# Strombegrenzung_RevC.net
KiCad netlist of a schematic drawn in EAGLE
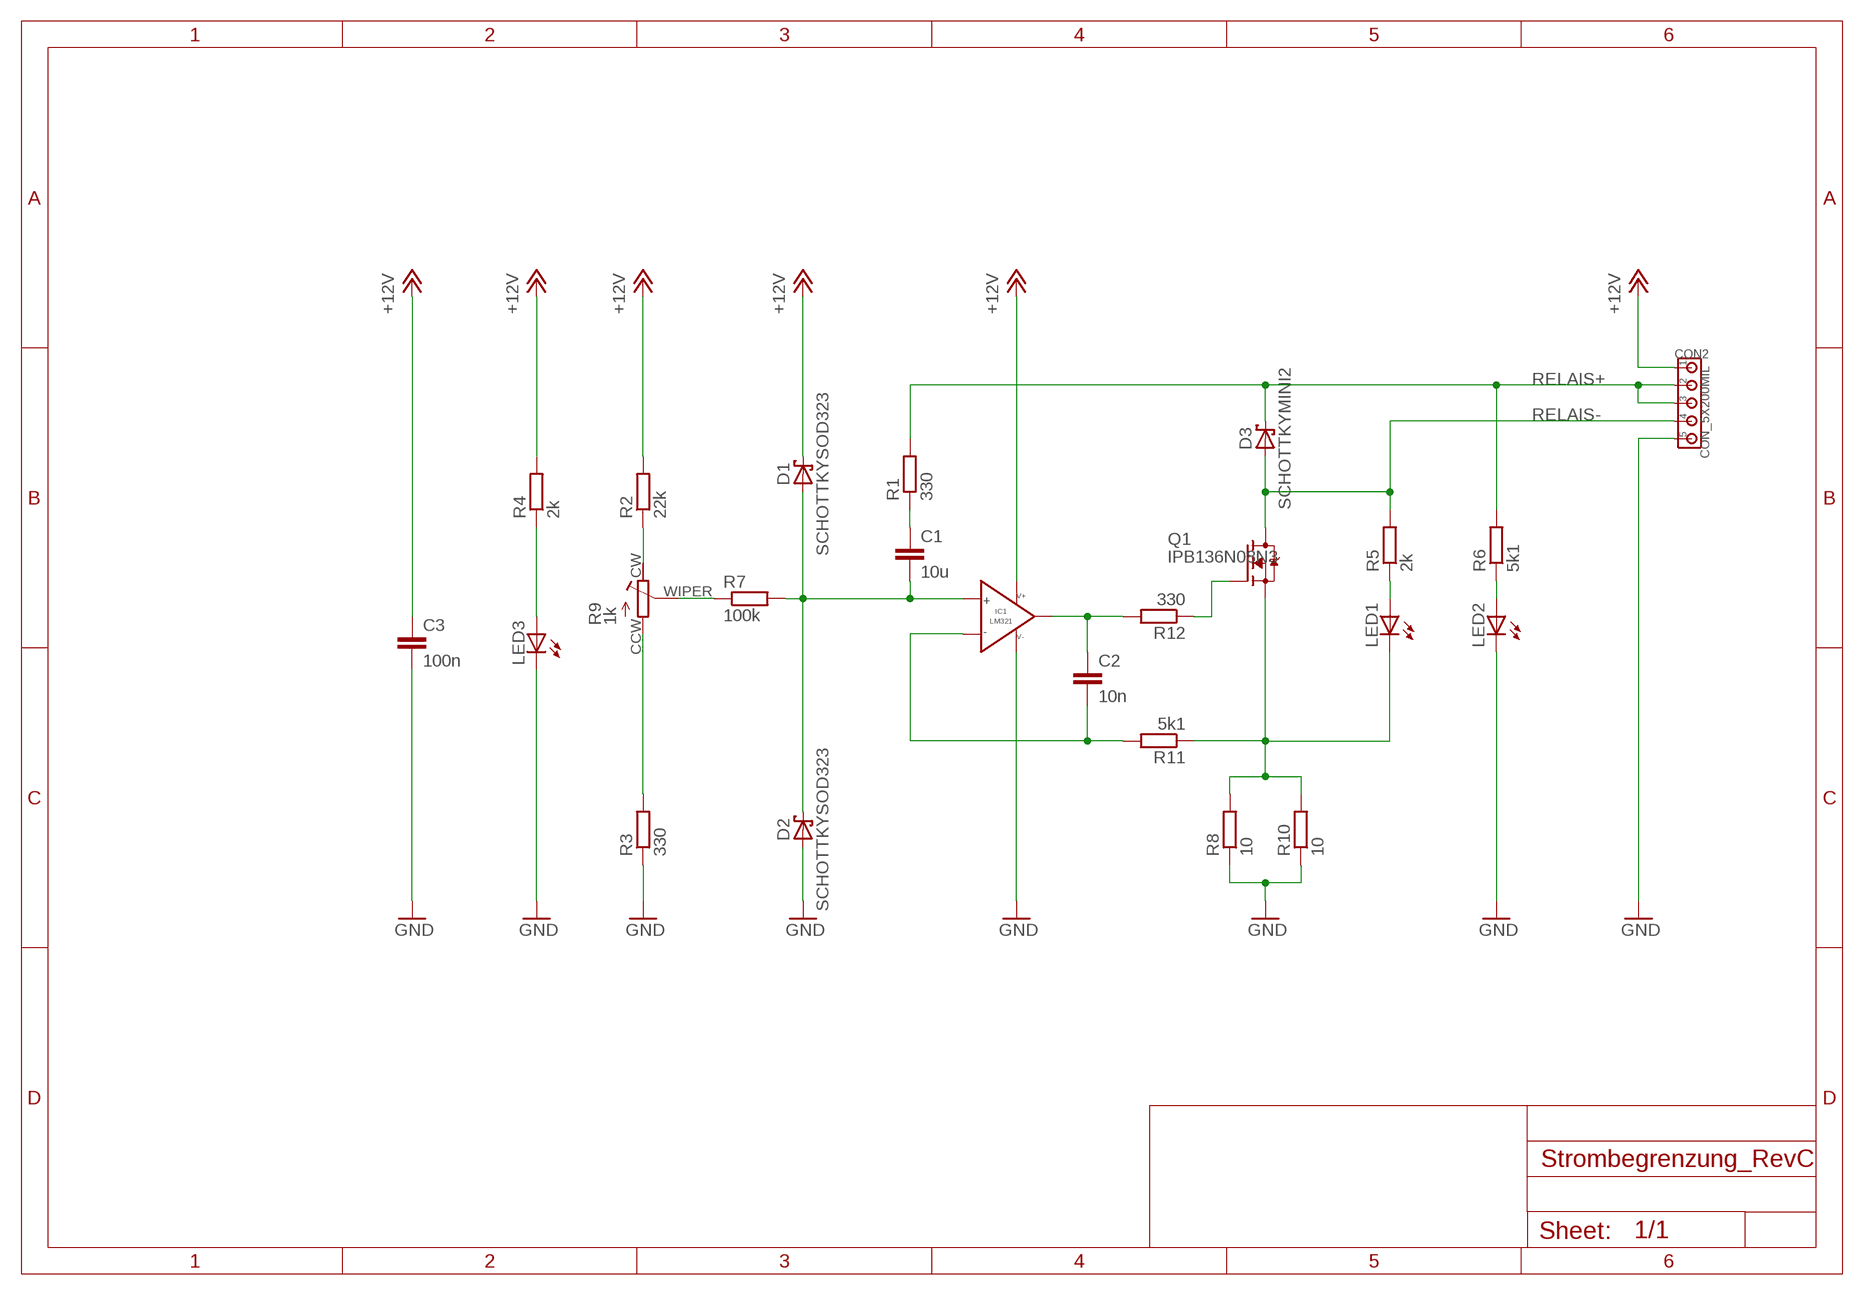
[diagram p0: schematic, sheet 1]

(export (version "E")
  (design (tool "Eeschema 10.0.6"))
  (components
    (comp (ref "C1")
      (value "10u")
      (footprint "eagle-import:C1206")
      (libsource (lib "eagle-import") (part "CC1206"))
    )
    (comp (ref "C2")
      (value "10n")
      (footprint "eagle-import:C0805")
      (libsource (lib "eagle-import") (part "CC0805"))
    )
    (comp (ref "C3")
      (value "100n")
      (footprint "eagle-import:C0805")
      (libsource (lib "eagle-import") (part "CC0805"))
    )
    (comp (ref "CON2")
      (value "CON_5X200MIL")
      (footprint "eagle-import:200MIL_5X")
      (libsource (lib "eagle-import") (part "CON_5X200MIL"))
    )
    (comp (ref "D1")
      (value "SCHOTTKYSOD323")
      (footprint "eagle-import:SOD323")
      (libsource (lib "eagle-import") (part "SCHOTTKYSOD323"))
    )
    (comp (ref "D2")
      (value "SCHOTTKYSOD323")
      (footprint "eagle-import:SOD323")
      (libsource (lib "eagle-import") (part "SCHOTTKYSOD323"))
    )
    (comp (ref "D3")
      (value "SCHOTTKYMINI2")
      (footprint "eagle-import:MINI2-F3-B")
      (libsource (lib "eagle-import") (part "SCHOTTKYMINI2"))
    )
    (comp (ref "IC1")
      (value "LM321")
      (footprint "eagle-import:SOT-23-5")
      (libsource (lib "eagle-import") (part "LM321"))
    )
    (comp (ref "LED1")
      (value "LED0805")
      (footprint "eagle-import:LED0805")
      (libsource (lib "eagle-import") (part "LED0805"))
    )
    (comp (ref "LED2")
      (value "LED0805")
      (footprint "eagle-import:LED0805")
      (libsource (lib "eagle-import") (part "LED0805"))
    )
    (comp (ref "LED3")
      (value "LED0805")
      (footprint "eagle-import:LED0805")
      (libsource (lib "eagle-import") (part "LED0805"))
    )
    (comp (ref "Q1")
      (value "IPB136N08N3")
      (footprint "eagle-import:TO263-3")
      (libsource (lib "eagle-import") (part "N-PWR-MOSFETTO263-3"))
    )
    (comp (ref "R1")
      (value "330")
      (footprint "eagle-import:R0805")
      (libsource (lib "eagle-import") (part "RESISTORR0805"))
    )
    (comp (ref "R2")
      (value "22k")
      (footprint "eagle-import:R0805")
      (libsource (lib "eagle-import") (part "RESISTORR0805"))
    )
    (comp (ref "R3")
      (value "330")
      (footprint "eagle-import:R0805")
      (libsource (lib "eagle-import") (part "RESISTORR0805"))
    )
    (comp (ref "R4")
      (value "2k")
      (footprint "eagle-import:R0805")
      (libsource (lib "eagle-import") (part "RESISTORR0805"))
    )
    (comp (ref "R5")
      (value "2k")
      (footprint "eagle-import:R0805")
      (libsource (lib "eagle-import") (part "RESISTORR0805"))
    )
    (comp (ref "R6")
      (value "5k1")
      (footprint "eagle-import:R0805")
      (libsource (lib "eagle-import") (part "RESISTORR0805"))
    )
    (comp (ref "R7")
      (value "100k")
      (footprint "eagle-import:R0805")
      (libsource (lib "eagle-import") (part "RESISTORR0805"))
    )
    (comp (ref "R8")
      (value "10")
      (footprint "eagle-import:R0805")
      (libsource (lib "eagle-import") (part "RESISTORR0805"))
    )
    (comp (ref "R9")
      (value "1k")
      (footprint "eagle-import:RTRIM3314G")
      (libsource (lib "eagle-import") (part "TRIMMER3314G"))
    )
    (comp (ref "R10")
      (value "10")
      (footprint "eagle-import:R0805")
      (libsource (lib "eagle-import") (part "RESISTORR0805"))
    )
    (comp (ref "R11")
      (value "5k1")
      (footprint "eagle-import:R0805")
      (libsource (lib "eagle-import") (part "RESISTORR0805"))
    )
    (comp (ref "R12")
      (value "330")
      (footprint "eagle-import:R0805")
      (libsource (lib "eagle-import") (part "RESISTORR0805"))
    )
  )
  (nets
    (net (code "1") (name "+12V") (class "Default")
      (node (ref "C3") (pin "1") (pinfunction "1_1") (pintype "passive"))
      (node (ref "CON2") (pin "1") (pinfunction "1_1") (pintype "passive"))
      (node (ref "D1") (pin "C") (pinfunction "C_C") (pintype "passive"))
      (node (ref "IC1") (pin "5") (pinfunction "V+_5") (pintype "input"))
      (node (ref "R2") (pin "2") (pinfunction "2_2") (pintype "passive"))
      (node (ref "R4") (pin "2") (pinfunction "2_2") (pintype "passive"))
    )
    (net (code "2") (name "/RELAIS+") (class "Default")
      (node (ref "CON2") (pin "2") (pinfunction "2_2") (pintype "passive"))
      (node (ref "CON2") (pin "3") (pinfunction "3_3") (pintype "passive"))
      (node (ref "D3") (pin "C") (pinfunction "C_C") (pintype "passive"))
      (node (ref "R1") (pin "2") (pinfunction "2_2") (pintype "passive"))
      (node (ref "R6") (pin "2") (pinfunction "2_2") (pintype "passive"))
    )
    (net (code "3") (name "/RELAIS-") (class "Default")
      (node (ref "CON2") (pin "4") (pinfunction "4_4") (pintype "passive"))
      (node (ref "D3") (pin "A") (pinfunction "A_A") (pintype "passive"))
      (node (ref "Q1") (pin "TAB") (pinfunction "D_TAB") (pintype "passive"))
      (node (ref "R5") (pin "2") (pinfunction "2_2") (pintype "passive"))
    )
    (net (code "4") (name "GND") (class "Default")
      (node (ref "C3") (pin "2") (pinfunction "2_2") (pintype "passive"))
      (node (ref "CON2") (pin "5") (pinfunction "5_5") (pintype "passive"))
      (node (ref "D2") (pin "A") (pinfunction "A_A") (pintype "passive"))
      (node (ref "IC1") (pin "2") (pinfunction "V-_2") (pintype "input"))
      (node (ref "LED2") (pin "C") (pinfunction "C_C") (pintype "passive"))
      (node (ref "LED3") (pin "C") (pinfunction "C_C") (pintype "passive"))
      (node (ref "R10") (pin "1") (pinfunction "1_1") (pintype "passive"))
      (node (ref "R3") (pin "1") (pinfunction "1_1") (pintype "passive"))
      (node (ref "R8") (pin "1") (pinfunction "1_1") (pintype "passive"))
    )
    (net (code "5") (name "Net-(C1-Pad1)") (class "Default")
      (node (ref "C1") (pin "1") (pinfunction "1_1") (pintype "passive"))
      (node (ref "R1") (pin "1") (pinfunction "1_1") (pintype "passive"))
    )
    (net (code "6") (name "Net-(IC1-IN+)") (class "Default")
      (node (ref "C1") (pin "2") (pinfunction "2_2") (pintype "passive"))
      (node (ref "D1") (pin "A") (pinfunction "A_A") (pintype "passive"))
      (node (ref "D2") (pin "C") (pinfunction "C_C") (pintype "passive"))
      (node (ref "IC1") (pin "1") (pinfunction "IN+_1") (pintype "input"))
      (node (ref "R7") (pin "2") (pinfunction "2_2") (pintype "passive"))
    )
    (net (code "7") (name "Net-(IC1-IN-)") (class "Default")
      (node (ref "C2") (pin "2") (pinfunction "2_2") (pintype "passive"))
      (node (ref "IC1") (pin "3") (pinfunction "IN-_3") (pintype "input"))
      (node (ref "R11") (pin "2") (pinfunction "2_2") (pintype "passive"))
    )
    (net (code "8") (name "Net-(IC1-VOUT)") (class "Default")
      (node (ref "C2") (pin "1") (pinfunction "1_1") (pintype "passive"))
      (node (ref "IC1") (pin "4") (pinfunction "VOUT_4") (pintype "output"))
      (node (ref "R12") (pin "2") (pinfunction "2_2") (pintype "passive"))
    )
    (net (code "9") (name "Net-(LED1-PadA)") (class "Default")
      (node (ref "LED1") (pin "A") (pinfunction "A_A") (pintype "passive"))
      (node (ref "R5") (pin "1") (pinfunction "1_1") (pintype "passive"))
    )
    (net (code "10") (name "Net-(LED2-PadA)") (class "Default")
      (node (ref "LED2") (pin "A") (pinfunction "A_A") (pintype "passive"))
      (node (ref "R6") (pin "1") (pinfunction "1_1") (pintype "passive"))
    )
    (net (code "11") (name "Net-(LED3-PadA)") (class "Default")
      (node (ref "LED3") (pin "A") (pinfunction "A_A") (pintype "passive"))
      (node (ref "R4") (pin "1") (pinfunction "1_1") (pintype "passive"))
    )
    (net (code "12") (name "Net-(Q1-G)") (class "Default")
      (node (ref "Q1") (pin "1") (pinfunction "G_1") (pintype "passive"))
      (node (ref "R12") (pin "1") (pinfunction "1_1") (pintype "passive"))
    )
    (net (code "13") (name "Net-(Q1-S)") (class "Default")
      (node (ref "LED1") (pin "C") (pinfunction "C_C") (pintype "passive"))
      (node (ref "Q1") (pin "3") (pinfunction "S_3") (pintype "passive"))
      (node (ref "R10") (pin "2") (pinfunction "2_2") (pintype "passive"))
      (node (ref "R11") (pin "1") (pinfunction "1_1") (pintype "passive"))
      (node (ref "R8") (pin "2") (pinfunction "2_2") (pintype "passive"))
    )
    (net (code "14") (name "Net-(R2-Pad1)") (class "Default")
      (node (ref "R2") (pin "1") (pinfunction "1_1") (pintype "passive"))
      (node (ref "R9") (pin "CW") (pinfunction "CW_CW") (pintype "passive"))
    )
    (net (code "15") (name "Net-(R3-Pad2)") (class "Default")
      (node (ref "R3") (pin "2") (pinfunction "2_2") (pintype "passive"))
      (node (ref "R9") (pin "CCW") (pinfunction "CCW_CCW") (pintype "passive"))
    )
    (net (code "16") (name "Net-(R7-Pad1)") (class "Default")
      (node (ref "R7") (pin "1") (pinfunction "1_1") (pintype "passive"))
      (node (ref "R9") (pin "WIPER") (pinfunction "WIPER_WIPER") (pintype "passive"))
    )
  )
)
